# Adafruit_ST25DV16.net
KiCad netlist of a schematic drawn in EAGLE
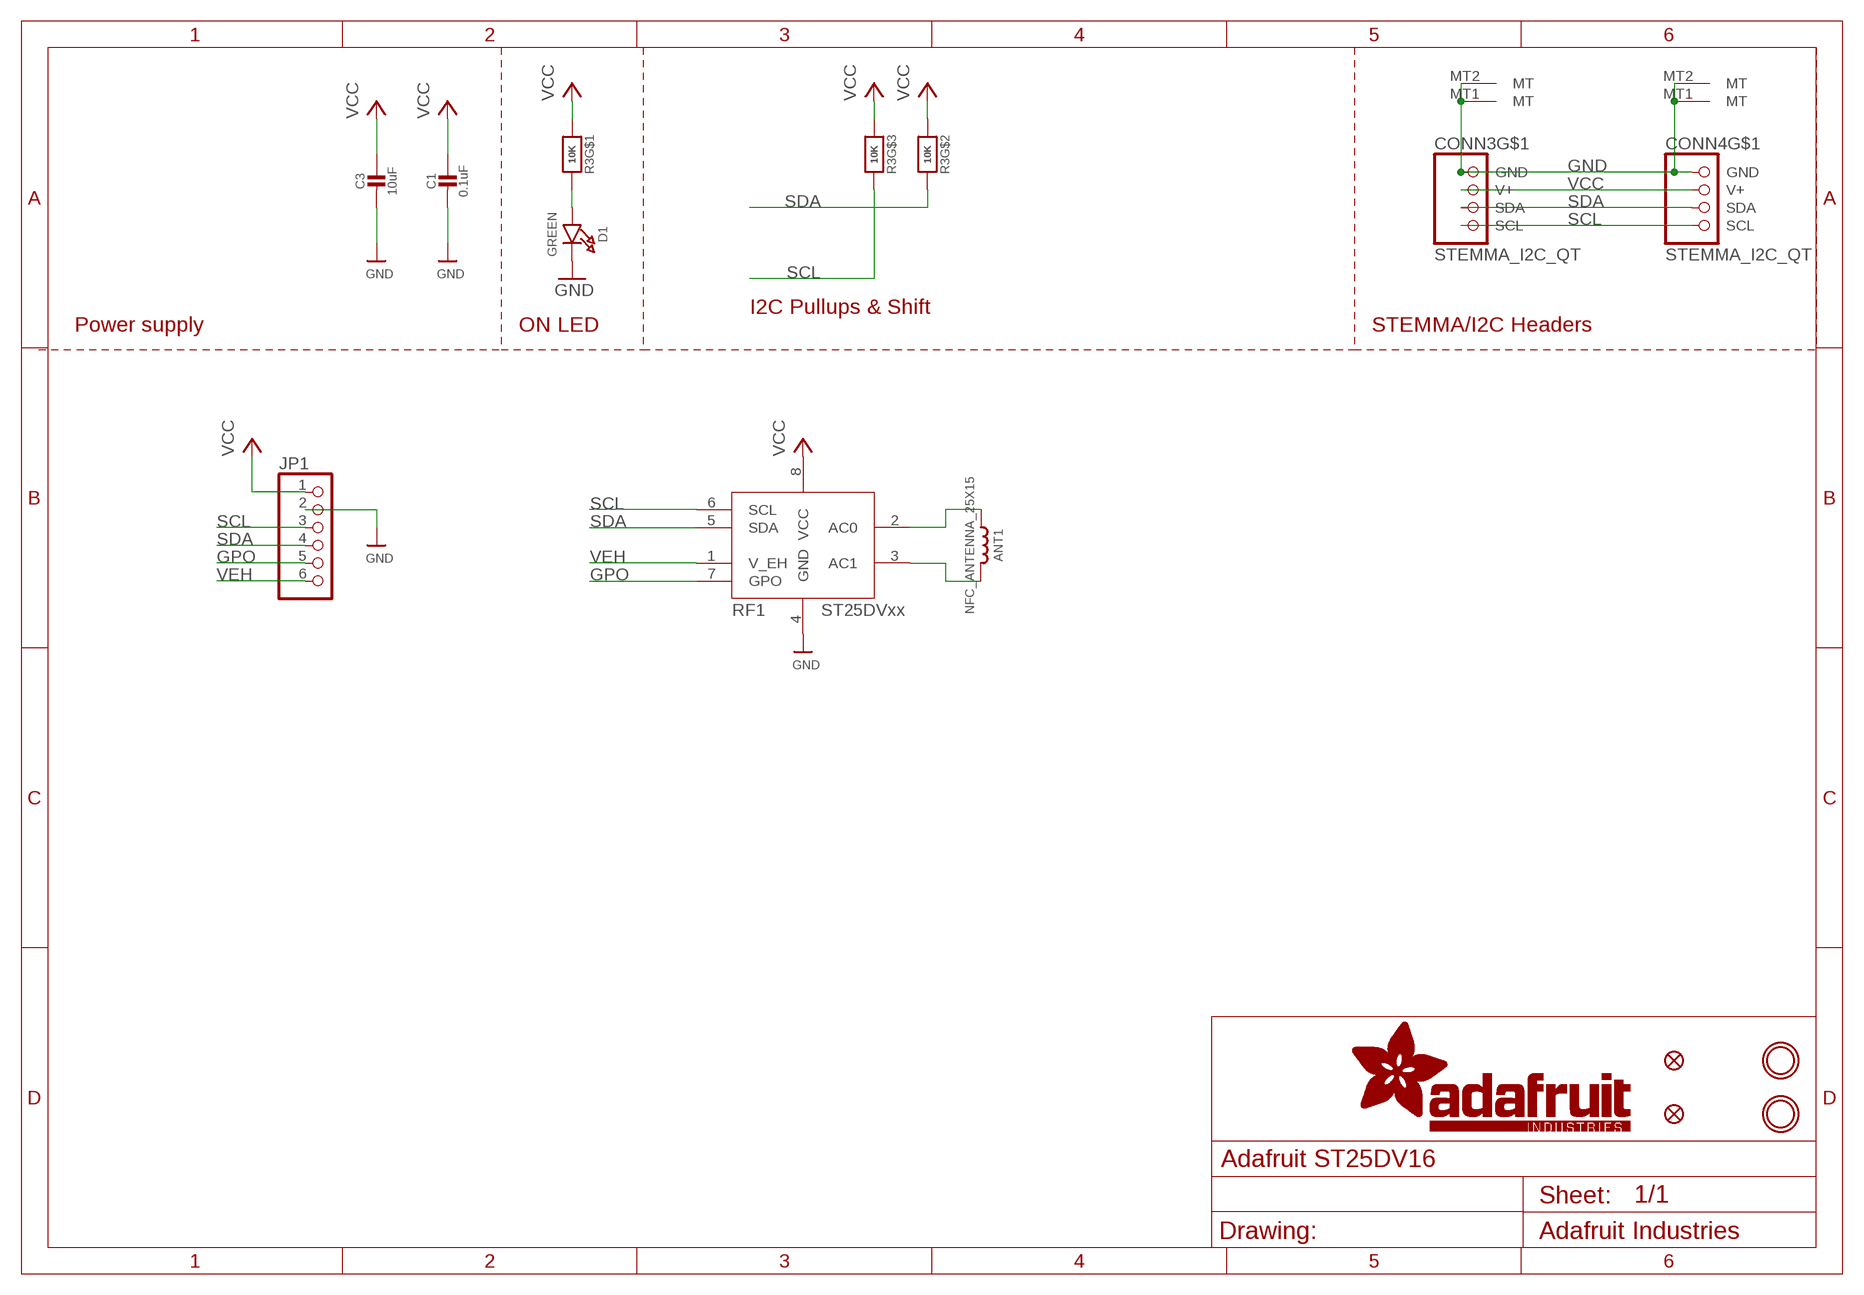
[diagram p0: schematic, sheet 1]

(export (version "E")
  (design (tool "Eeschema 10.0.6"))
  (components
    (comp (ref "ANT1")
      (value "NFC_ANTENNA_25X15")
      (footprint "eagle-import:NFCANT_25X15")
      (libsource (lib "eagle-import") (part "NFC_ANTENNA_25X15"))
    )
    (comp (ref "C1")
      (value "0.1uF")
      (footprint "eagle-import:0603-NO")
      (libsource (lib "eagle-import") (part "CAP_CERAMIC0603_NO"))
    )
    (comp (ref "C3")
      (value "10uF")
      (footprint "eagle-import:0805-NO")
      (libsource (lib "eagle-import") (part "CAP_CERAMIC0805-NOOUTLINE"))
    )
    (comp (ref "CONN3")
      (value "STEMMA_I2C_QT")
      (footprint "eagle-import:JST_SH4")
      (libsource (lib "eagle-import") (part "STEMMA_I2C_QT"))
    )
    (comp (ref "CONN4")
      (value "STEMMA_I2C_QT")
      (footprint "eagle-import:JST_SH4")
      (libsource (lib "eagle-import") (part "STEMMA_I2C_QT"))
    )
    (comp (ref "D1")
      (value "GREEN")
      (footprint "eagle-import:CHIPLED_0603_NOOUTLINE")
      (libsource (lib "eagle-import") (part "LED0603_NOOUTLINE"))
    )
    (comp (ref "FID3")
      (value "FIDUCIAL_1MM")
      (footprint "eagle-import:FIDUCIAL_1MM")
      (libsource (lib "eagle-import") (part "FIDUCIAL_1MM"))
    )
    (comp (ref "FID4")
      (value "FIDUCIAL_1MM")
      (footprint "eagle-import:FIDUCIAL_1MM")
      (libsource (lib "eagle-import") (part "FIDUCIAL_1MM"))
    )
    (comp (ref "JP1")
      (value "HEADER-1X670MIL")
      (footprint "eagle-import:1X06_ROUND_70")
      (libsource (lib "eagle-import") (part "HEADER-1X670MIL"))
    )
    (comp (ref "R3")
      (value "10K")
      (footprint "eagle-import:RESPACK_4X0603")
      (libsource (lib "eagle-import") (part "RESISTOR_4PACK"))
    )
    (comp (ref "RF1")
      (value "ST25DVXX_TSSOP")
      (footprint "eagle-import:TSSOP8-4.4MM")
      (libsource (lib "eagle-import") (part "ST25DVXX_TSSOP"))
    )
    (comp (ref "U$19")
      (value "MOUNTINGHOLE2.5")
      (footprint "eagle-import:MOUNTINGHOLE_2.5_PLATED")
      (libsource (lib "eagle-import") (part "MOUNTINGHOLE2.5"))
    )
    (comp (ref "U$21")
      (value "MOUNTINGHOLE2.5")
      (footprint "eagle-import:MOUNTINGHOLE_2.5_PLATED")
      (libsource (lib "eagle-import") (part "MOUNTINGHOLE2.5"))
    )
  )
  (nets
    (net (code "1") (name "/GPO") (class "Default")
      (node (ref "JP1") (pin "5") (pinfunction "5_5") (pintype "passive"))
      (node (ref "RF1") (pin "7") (pinfunction "GPO_7") (pintype "output"))
    )
    (net (code "2") (name "/SCL") (class "Default")
      (node (ref "CONN3") (pin "4") (pinfunction "SCL_4") (pintype "passive"))
      (node (ref "CONN4") (pin "4") (pinfunction "SCL_4") (pintype "passive"))
      (node (ref "JP1") (pin "3") (pinfunction "3_3") (pintype "passive"))
      (node (ref "R3") (pin "6") (pinfunction "2_6") (pintype "passive"))
      (node (ref "RF1") (pin "6") (pinfunction "SCL_6") (pintype "bidirectional"))
    )
    (net (code "3") (name "/SDA") (class "Default")
      (node (ref "CONN3") (pin "3") (pinfunction "SDA_3") (pintype "passive"))
      (node (ref "CONN4") (pin "3") (pinfunction "SDA_3") (pintype "passive"))
      (node (ref "JP1") (pin "4") (pinfunction "4_4") (pintype "passive"))
      (node (ref "R3") (pin "7") (pinfunction "2_7") (pintype "passive"))
      (node (ref "RF1") (pin "5") (pinfunction "SDA_5") (pintype "bidirectional"))
    )
    (net (code "4") (name "/VEH") (class "Default")
      (node (ref "JP1") (pin "6") (pinfunction "6_6") (pintype "passive"))
      (node (ref "RF1") (pin "1") (pinfunction "V_EH_1") (pintype "output"))
    )
    (net (code "5") (name "GND") (class "Default")
      (node (ref "C1") (pin "2") (pinfunction "2_2") (pintype "passive"))
      (node (ref "C3") (pin "2") (pinfunction "2_2") (pintype "passive"))
      (node (ref "CONN3") (pin "1") (pinfunction "GND_1") (pintype "passive"))
      (node (ref "CONN3") (pin "MT1") (pinfunction "MT_MT1") (pintype "bidirectional"))
      (node (ref "CONN3") (pin "MT2") (pinfunction "MT_MT2") (pintype "bidirectional"))
      (node (ref "CONN4") (pin "1") (pinfunction "GND_1") (pintype "passive"))
      (node (ref "CONN4") (pin "MT1") (pinfunction "MT_MT1") (pintype "bidirectional"))
      (node (ref "CONN4") (pin "MT2") (pinfunction "MT_MT2") (pintype "bidirectional"))
      (node (ref "D1") (pin "C") (pinfunction "C_C") (pintype "passive"))
      (node (ref "JP1") (pin "2") (pinfunction "2_2") (pintype "passive"))
      (node (ref "RF1") (pin "4") (pinfunction "GND_4") (pintype "power_in"))
    )
    (net (code "6") (name "Net-(ANT1-1)") (class "Default")
      (node (ref "ANT1") (pin "P$1") (pinfunction "1_P$1") (pintype "passive"))
      (node (ref "RF1") (pin "3") (pinfunction "AC1_3") (pintype "passive"))
    )
    (net (code "7") (name "Net-(ANT1-2)") (class "Default")
      (node (ref "ANT1") (pin "P$2") (pinfunction "2_P$2") (pintype "passive"))
      (node (ref "RF1") (pin "2") (pinfunction "AC0_2") (pintype "passive"))
    )
    (net (code "8") (name "Net-(R3A-2)") (class "Default")
      (node (ref "D1") (pin "A") (pinfunction "A_A") (pintype "passive"))
      (node (ref "R3") (pin "8") (pinfunction "2_8") (pintype "passive"))
    )
    (net (code "9") (name "VCC") (class "Default")
      (node (ref "C1") (pin "1") (pinfunction "1_1") (pintype "passive"))
      (node (ref "C3") (pin "1") (pinfunction "1_1") (pintype "passive"))
      (node (ref "CONN3") (pin "2") (pinfunction "V+_2") (pintype "passive"))
      (node (ref "CONN4") (pin "2") (pinfunction "V+_2") (pintype "passive"))
      (node (ref "JP1") (pin "1") (pinfunction "1_1") (pintype "passive"))
      (node (ref "R3") (pin "1") (pinfunction "1_1") (pintype "passive"))
      (node (ref "R3") (pin "2") (pinfunction "1_2") (pintype "passive"))
      (node (ref "R3") (pin "3") (pinfunction "1_3") (pintype "passive"))
      (node (ref "RF1") (pin "8") (pinfunction "VCC_8") (pintype "power_in"))
    )
  )
)
